# GIVmon_v1_0.net
KiCad netlist of a schematic drawn in EAGLE
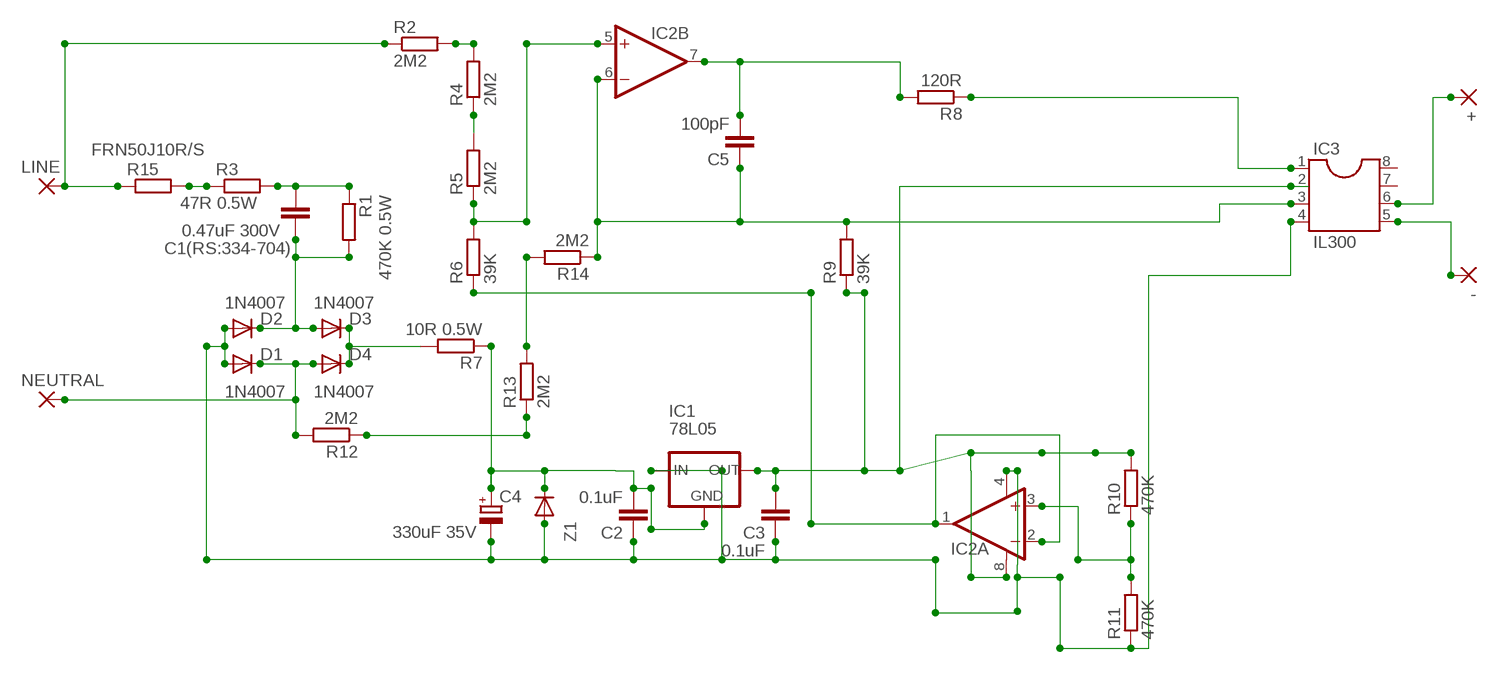
[diagram p0: schematic, sheet 1]

(export (version "E")
  (design (tool "Eeschema 10.0.6"))
  (components
    (comp (ref "+")
      (value "3,81/1,4")
      (footprint "eagle-import:3,81_1,4")
      (libsource (lib "eagle-import") (part "3,81/1,4"))
    )
    (comp (ref "-")
      (value "3,81/1,4")
      (footprint "eagle-import:3,81_1,4")
      (libsource (lib "eagle-import") (part "3,81/1,4"))
    )
    (comp (ref "C1(RS:334-704)")
      (value "0.47uF 300V")
      (footprint "eagle-import:C225-108X268")
      (libsource (lib "eagle-import") (part "C-EU225-108X268"))
    )
    (comp (ref "C2")
      (value "0.1uF")
      (footprint "eagle-import:C050-024X044")
      (libsource (lib "eagle-import") (part "C-EU050-024X044"))
    )
    (comp (ref "C3")
      (value "0.1uF")
      (footprint "eagle-import:C050-024X044")
      (libsource (lib "eagle-import") (part "C-EU050-024X044"))
    )
    (comp (ref "C4")
      (value "330uF 35V")
      (footprint "eagle-import:E5-6")
      (libsource (lib "eagle-import") (part "CPOL-EUE5-6"))
    )
    (comp (ref "C5")
      (value "100pF")
      (footprint "eagle-import:C025-024X044")
      (libsource (lib "eagle-import") (part "C-EU025-024X044"))
    )
    (comp (ref "D1")
      (value "1N4007")
      (footprint "eagle-import:DIODE-1N4001")
      (libsource (lib "eagle-import") (part "DIODEPTH"))
    )
    (comp (ref "D2")
      (value "1N4007")
      (footprint "eagle-import:DIODE-1N4001")
      (libsource (lib "eagle-import") (part "DIODEPTH"))
    )
    (comp (ref "D3")
      (value "1N4007")
      (footprint "eagle-import:DIODE-1N4001")
      (libsource (lib "eagle-import") (part "DIODEPTH"))
    )
    (comp (ref "D4")
      (value "1N4007")
      (footprint "eagle-import:DIODE-1N4001")
      (libsource (lib "eagle-import") (part "DIODEPTH"))
    )
    (comp (ref "IC1")
      (value "78L05")
      (footprint "eagle-import:TO-92")
      (libsource (lib "eagle-import") (part "V_REG_78XXTO-92"))
    )
    (comp (ref "IC2")
      (value "OPAMP-DUALDIP")
      (footprint "eagle-import:DIP08")
      (libsource (lib "eagle-import") (part "OPAMP-DUALDIP"))
    )
    (comp (ref "IC3")
      (value "IL300")
      (footprint "eagle-import:DIL08")
      (libsource (lib "eagle-import") (part "DIL8"))
    )
    (comp (ref "LINE")
      (value "3,81/1,4")
      (footprint "eagle-import:3,81_1,4")
      (libsource (lib "eagle-import") (part "3,81/1,4"))
    )
    (comp (ref "NEUTRAL")
      (value "3,81/1,4")
      (footprint "eagle-import:3,81_1,4")
      (libsource (lib "eagle-import") (part "3,81/1,4"))
    )
    (comp (ref "R1")
      (value "470K 0.5W")
      (footprint "eagle-import:0204_7")
      (libsource (lib "eagle-import") (part "R-EU_0204/7"))
    )
    (comp (ref "R2")
      (value "2M2")
      (footprint "eagle-import:0204_7")
      (libsource (lib "eagle-import") (part "R-EU_0204/7"))
    )
    (comp (ref "R3")
      (value "47R 0.5W")
      (footprint "eagle-import:0204_7")
      (libsource (lib "eagle-import") (part "R-EU_0204/7"))
    )
    (comp (ref "R4")
      (value "2M2")
      (footprint "eagle-import:0204_7")
      (libsource (lib "eagle-import") (part "R-EU_0204/7"))
    )
    (comp (ref "R5")
      (value "2M2")
      (footprint "eagle-import:0204_7")
      (libsource (lib "eagle-import") (part "R-EU_0204/7"))
    )
    (comp (ref "R6")
      (value "39K")
      (footprint "eagle-import:0204_7")
      (libsource (lib "eagle-import") (part "R-EU_0204/7"))
    )
    (comp (ref "R7")
      (value "10R 0.5W")
      (footprint "eagle-import:0204_7")
      (libsource (lib "eagle-import") (part "R-EU_0204/7"))
    )
    (comp (ref "R8")
      (value "120R")
      (footprint "eagle-import:0204_7")
      (libsource (lib "eagle-import") (part "R-EU_0204/7"))
    )
    (comp (ref "R9")
      (value "39K")
      (footprint "eagle-import:0204_7")
      (libsource (lib "eagle-import") (part "R-EU_0204/7"))
    )
    (comp (ref "R10")
      (value "470K")
      (footprint "eagle-import:0204_7")
      (libsource (lib "eagle-import") (part "R-EU_0204/7"))
    )
    (comp (ref "R11")
      (value "470K")
      (footprint "eagle-import:0204_7")
      (libsource (lib "eagle-import") (part "R-EU_0204/7"))
    )
    (comp (ref "R12")
      (value "2M2")
      (footprint "eagle-import:0204_7")
      (libsource (lib "eagle-import") (part "R-EU_0204/7"))
    )
    (comp (ref "R13")
      (value "2M2")
      (footprint "eagle-import:0204_7")
      (libsource (lib "eagle-import") (part "R-EU_0204/7"))
    )
    (comp (ref "R14")
      (value "2M2")
      (footprint "eagle-import:0204_7")
      (libsource (lib "eagle-import") (part "R-EU_0204/7"))
    )
    (comp (ref "R15")
      (value "FRN50J10R/S")
      (footprint "eagle-import:0204_7")
      (libsource (lib "eagle-import") (part "R-EU_0204/7"))
    )
    (comp (ref "Z1")
      (value "1N59278")
      (footprint "eagle-import:DIODE-1N4001")
      (libsource (lib "eagle-import") (part "DIODEPTH"))
    )
  )
  (nets
    (net (code "1") (name "Net-(+-P)") (class "Default")
      (node (ref "+") (pin "1") (pinfunction "P_1") (pintype "passive"))
      (node (ref "IC3") (pin "6") (pinfunction "6_6") (pintype "passive"))
    )
    (net (code "2") (name "Net-(--P)") (class "Default")
      (node (ref "-") (pin "1") (pinfunction "P_1") (pintype "passive"))
      (node (ref "IC3") (pin "5") (pinfunction "5_5") (pintype "passive"))
    )
    (net (code "3") (name "Net-(C1(RS:334-704)-Pad1)") (class "Default")
      (node (ref "C1(RS:334-704)") (pin "1") (pinfunction "1_1") (pintype "passive"))
      (node (ref "R1") (pin "1") (pinfunction "1_1") (pintype "passive"))
      (node (ref "R3") (pin "2") (pinfunction "2_2") (pintype "passive"))
    )
    (net (code "4") (name "Net-(C1(RS:334-704)-Pad2)") (class "Default")
      (node (ref "C1(RS:334-704)") (pin "2") (pinfunction "2_2") (pintype "passive"))
      (node (ref "D2") (pin "C") (pinfunction "C_C") (pintype "passive"))
      (node (ref "D3") (pin "A") (pinfunction "A_A") (pintype "passive"))
      (node (ref "R1") (pin "2") (pinfunction "2_2") (pintype "passive"))
    )
    (net (code "5") (name "Net-(D3-PadC)") (class "Default")
      (node (ref "D3") (pin "C") (pinfunction "C_C") (pintype "passive"))
      (node (ref "D4") (pin "C") (pinfunction "C_C") (pintype "passive"))
      (node (ref "R7") (pin "2") (pinfunction "2_2") (pintype "passive"))
    )
    (net (code "6") (name "Net-(IC1-GND)") (class "Default")
      (node (ref "C2") (pin "2") (pinfunction "2_2") (pintype "passive"))
      (node (ref "C4") (pin "+") (pinfunction "+_+") (pintype "passive"))
      (node (ref "IC1") (pin "1") (pinfunction "GND_1") (pintype "input"))
      (node (ref "R7") (pin "1") (pinfunction "1_1") (pintype "passive"))
      (node (ref "Z1") (pin "C") (pinfunction "C_C") (pintype "passive"))
    )
    (net (code "7") (name "Net-(IC1-IN)") (class "Default")
      (node (ref "C2") (pin "1") (pinfunction "1_1") (pintype "passive"))
      (node (ref "C3") (pin "1") (pinfunction "1_1") (pintype "passive"))
      (node (ref "C4") (pin "-") (pinfunction "-_-") (pintype "passive"))
      (node (ref "D1") (pin "A") (pinfunction "A_A") (pintype "passive"))
      (node (ref "D2") (pin "A") (pinfunction "A_A") (pintype "passive"))
      (node (ref "IC1") (pin "2") (pinfunction "IN_2") (pintype "input"))
      (node (ref "IC2") (pin "4") (pinfunction "V-_4") (pintype "power_in"))
      (node (ref "IC3") (pin "4") (pinfunction "4_4") (pintype "passive"))
      (node (ref "R11") (pin "1") (pinfunction "1_1") (pintype "passive"))
      (node (ref "Z1") (pin "A") (pinfunction "A_A") (pintype "passive"))
    )
    (net (code "8") (name "Net-(IC1-OUT)") (class "Default")
      (node (ref "C3") (pin "2") (pinfunction "2_2") (pintype "passive"))
      (node (ref "IC1") (pin "3") (pinfunction "OUT_3") (pintype "output"))
      (node (ref "IC2") (pin "8") (pinfunction "V+_8") (pintype "power_in"))
      (node (ref "IC3") (pin "2") (pinfunction "2_2") (pintype "passive"))
      (node (ref "R10") (pin "2") (pinfunction "2_2") (pintype "passive"))
      (node (ref "R9") (pin "1") (pinfunction "1_1") (pintype "passive"))
    )
    (net (code "9") (name "Net-(IC2A-+IN)") (class "Default")
      (node (ref "IC2") (pin "3") (pinfunction "+IN_3") (pintype "input"))
      (node (ref "R10") (pin "1") (pinfunction "1_1") (pintype "passive"))
      (node (ref "R11") (pin "2") (pinfunction "2_2") (pintype "passive"))
    )
    (net (code "10") (name "Net-(IC2A--IN)") (class "Default")
      (node (ref "IC2") (pin "1") (pinfunction "OUT_1") (pintype "output"))
      (node (ref "IC2") (pin "2") (pinfunction "-IN_2") (pintype "input"))
      (node (ref "R6") (pin "1") (pinfunction "1_1") (pintype "passive"))
    )
    (net (code "11") (name "Net-(IC2B-+IN)") (class "Default")
      (node (ref "IC2") (pin "5") (pinfunction "+IN_5") (pintype "input"))
      (node (ref "R5") (pin "1") (pinfunction "1_1") (pintype "passive"))
      (node (ref "R6") (pin "2") (pinfunction "2_2") (pintype "passive"))
    )
    (net (code "12") (name "Net-(IC2B--IN)") (class "Default")
      (node (ref "C5") (pin "1") (pinfunction "1_1") (pintype "passive"))
      (node (ref "IC2") (pin "6") (pinfunction "-IN_6") (pintype "input"))
      (node (ref "IC3") (pin "3") (pinfunction "3_3") (pintype "passive"))
      (node (ref "R14") (pin "1") (pinfunction "1_1") (pintype "passive"))
      (node (ref "R9") (pin "2") (pinfunction "2_2") (pintype "passive"))
    )
    (net (code "13") (name "Net-(IC2B-OUT)") (class "Default")
      (node (ref "C5") (pin "2") (pinfunction "2_2") (pintype "passive"))
      (node (ref "IC2") (pin "7") (pinfunction "OUT_7") (pintype "output"))
      (node (ref "R8") (pin "2") (pinfunction "2_2") (pintype "passive"))
    )
    (net (code "14") (name "Net-(IC3-Pad1)") (class "Default")
      (node (ref "IC3") (pin "1") (pinfunction "1_1") (pintype "passive"))
      (node (ref "R8") (pin "1") (pinfunction "1_1") (pintype "passive"))
    )
    (net (code "15") (name "Net-(LINE-P)") (class "Default")
      (node (ref "LINE") (pin "1") (pinfunction "P_1") (pintype "passive"))
      (node (ref "R15") (pin "1") (pinfunction "1_1") (pintype "passive"))
      (node (ref "R2") (pin "1") (pinfunction "1_1") (pintype "passive"))
    )
    (net (code "16") (name "Net-(NEUTRAL-P)") (class "Default")
      (node (ref "D1") (pin "C") (pinfunction "C_C") (pintype "passive"))
      (node (ref "D4") (pin "A") (pinfunction "A_A") (pintype "passive"))
      (node (ref "NEUTRAL") (pin "1") (pinfunction "P_1") (pintype "passive"))
      (node (ref "R12") (pin "2") (pinfunction "2_2") (pintype "passive"))
    )
    (net (code "17") (name "Net-(R2-Pad2)") (class "Default")
      (node (ref "R2") (pin "2") (pinfunction "2_2") (pintype "passive"))
      (node (ref "R4") (pin "2") (pinfunction "2_2") (pintype "passive"))
    )
    (net (code "18") (name "Net-(R4-Pad1)") (class "Default")
      (node (ref "R4") (pin "1") (pinfunction "1_1") (pintype "passive"))
      (node (ref "R5") (pin "2") (pinfunction "2_2") (pintype "passive"))
    )
    (net (code "19") (name "Net-(R12-Pad1)") (class "Default")
      (node (ref "R12") (pin "1") (pinfunction "1_1") (pintype "passive"))
      (node (ref "R13") (pin "1") (pinfunction "1_1") (pintype "passive"))
    )
    (net (code "20") (name "Net-(R13-Pad2)") (class "Default")
      (node (ref "R13") (pin "2") (pinfunction "2_2") (pintype "passive"))
      (node (ref "R14") (pin "2") (pinfunction "2_2") (pintype "passive"))
    )
    (net (code "21") (name "Net-(R15-Pad2)") (class "Default")
      (node (ref "R15") (pin "2") (pinfunction "2_2") (pintype "passive"))
      (node (ref "R3") (pin "1") (pinfunction "1_1") (pintype "passive"))
    )
    (net (code "22") (name "unconnected-(IC3-Pad7)") (class "Default")
      (node (ref "IC3") (pin "7") (pinfunction "7_7") (pintype "passive"))
    )
    (net (code "23") (name "unconnected-(IC3-Pad8)") (class "Default")
      (node (ref "IC3") (pin "8") (pinfunction "8_8") (pintype "passive"))
    )
  )
)
